# FLEX_DISPLAY.net
KiCad netlist of a schematic drawn in EAGLE
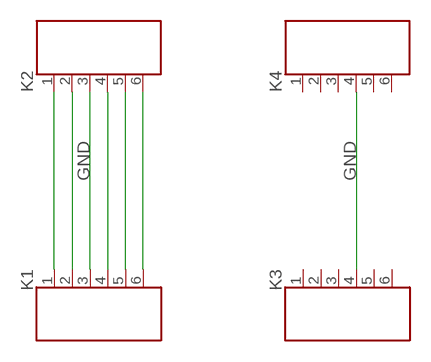
[diagram p0: schematic, sheet 1]

(export (version "E")
  (design (tool "Eeschema 10.0.6"))
  (components
    (comp (ref "K1")
      (value "FLEX6")
      (footprint "eagle-import:FLEX6")
      (libsource (lib "eagle-import") (part "FLEX6"))
    )
    (comp (ref "K2")
      (value "FLEX6")
      (footprint "eagle-import:FLEX6")
      (libsource (lib "eagle-import") (part "FLEX6"))
    )
    (comp (ref "K3")
      (value "FLEX6")
      (footprint "eagle-import:FLEX6")
      (libsource (lib "eagle-import") (part "FLEX6"))
    )
    (comp (ref "K4")
      (value "FLEX6")
      (footprint "eagle-import:FLEX6")
      (libsource (lib "eagle-import") (part "FLEX6"))
    )
  )
  (nets
    (net (code "1") (name "/GND") (class "Default")
      (node (ref "K1") (pin "3") (pinfunction "3_3") (pintype "passive"))
      (node (ref "K2") (pin "3") (pinfunction "3_3") (pintype "passive"))
      (node (ref "K3") (pin "4") (pinfunction "4_4") (pintype "passive"))
      (node (ref "K4") (pin "4") (pinfunction "4_4") (pintype "passive"))
    )
    (net (code "2") (name "Net-(K1-Pad1)") (class "Default")
      (node (ref "K1") (pin "1") (pinfunction "1_1") (pintype "passive"))
      (node (ref "K2") (pin "1") (pinfunction "1_1") (pintype "passive"))
    )
    (net (code "3") (name "Net-(K1-Pad2)") (class "Default")
      (node (ref "K1") (pin "2") (pinfunction "2_2") (pintype "passive"))
      (node (ref "K2") (pin "2") (pinfunction "2_2") (pintype "passive"))
    )
    (net (code "4") (name "Net-(K1-Pad4)") (class "Default")
      (node (ref "K1") (pin "4") (pinfunction "4_4") (pintype "passive"))
      (node (ref "K2") (pin "4") (pinfunction "4_4") (pintype "passive"))
    )
    (net (code "5") (name "Net-(K1-Pad5)") (class "Default")
      (node (ref "K1") (pin "5") (pinfunction "5_5") (pintype "passive"))
      (node (ref "K2") (pin "5") (pinfunction "5_5") (pintype "passive"))
    )
    (net (code "6") (name "Net-(K1-Pad6)") (class "Default")
      (node (ref "K1") (pin "6") (pinfunction "6_6") (pintype "passive"))
      (node (ref "K2") (pin "6") (pinfunction "6_6") (pintype "passive"))
    )
    (net (code "7") (name "unconnected-(K3-Pad1)") (class "Default")
      (node (ref "K3") (pin "1") (pinfunction "1_1") (pintype "passive"))
    )
    (net (code "8") (name "unconnected-(K3-Pad2)") (class "Default")
      (node (ref "K3") (pin "2") (pinfunction "2_2") (pintype "passive"))
    )
    (net (code "9") (name "unconnected-(K3-Pad3)") (class "Default")
      (node (ref "K3") (pin "3") (pinfunction "3_3") (pintype "passive"))
    )
    (net (code "10") (name "unconnected-(K3-Pad5)") (class "Default")
      (node (ref "K3") (pin "5") (pinfunction "5_5") (pintype "passive"))
    )
    (net (code "11") (name "unconnected-(K3-Pad6)") (class "Default")
      (node (ref "K3") (pin "6") (pinfunction "6_6") (pintype "passive"))
    )
    (net (code "12") (name "unconnected-(K4-Pad1)") (class "Default")
      (node (ref "K4") (pin "1") (pinfunction "1_1") (pintype "passive"))
    )
    (net (code "13") (name "unconnected-(K4-Pad2)") (class "Default")
      (node (ref "K4") (pin "2") (pinfunction "2_2") (pintype "passive"))
    )
    (net (code "14") (name "unconnected-(K4-Pad3)") (class "Default")
      (node (ref "K4") (pin "3") (pinfunction "3_3") (pintype "passive"))
    )
    (net (code "15") (name "unconnected-(K4-Pad5)") (class "Default")
      (node (ref "K4") (pin "5") (pinfunction "5_5") (pintype "passive"))
    )
    (net (code "16") (name "unconnected-(K4-Pad6)") (class "Default")
      (node (ref "K4") (pin "6") (pinfunction "6_6") (pintype "passive"))
    )
  )
)
